# LIDO-HW_100_InputStage.net
KiCad netlist of a schematic drawn in Altium Designer
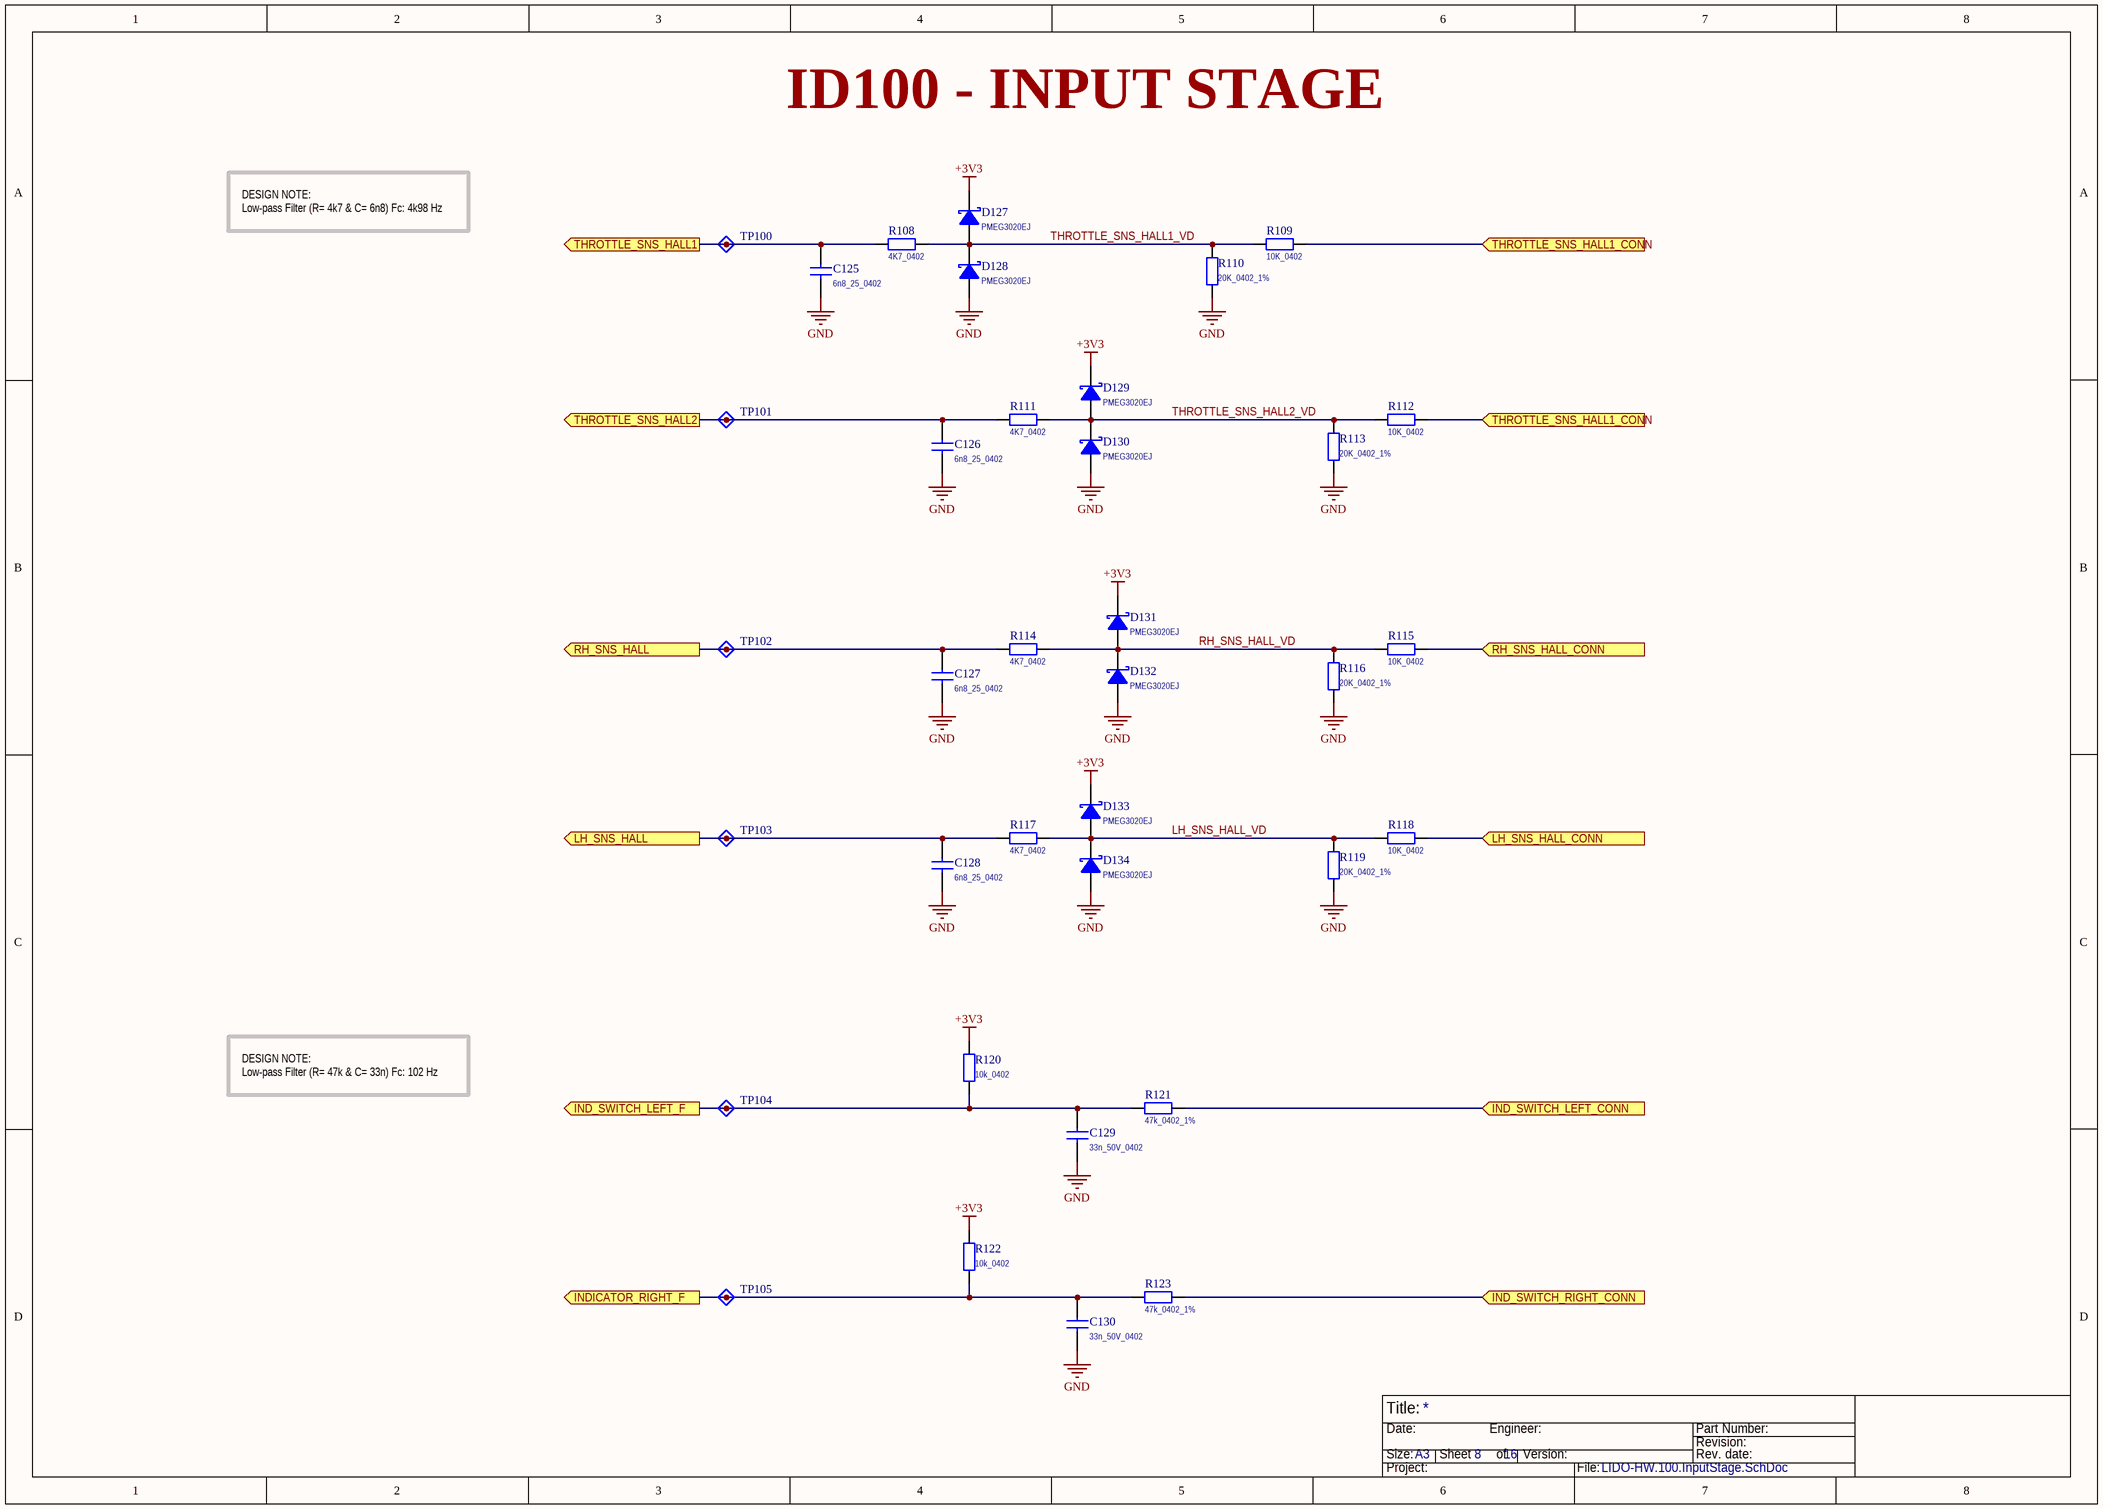
[diagram p0: LIDO-HW.100.InputStage.SchDoc]

(export (version "E")
  (design (tool "Eeschema 10.0.6"))
  (components
    (comp (ref "C125")
      (value "6n8_25_0402")
      (description "Ceramic CAP Symbol")
      (libsource (lib "01_Capacitors") (part "Ceramic"))
    )
    (comp (ref "C126")
      (value "6n8_25_0402")
      (description "Ceramic CAP Symbol")
      (libsource (lib "01_Capacitors") (part "Ceramic"))
    )
    (comp (ref "C127")
      (value "6n8_25_0402")
      (description "Ceramic CAP Symbol")
      (libsource (lib "01_Capacitors") (part "Ceramic"))
    )
    (comp (ref "C128")
      (value "6n8_25_0402")
      (description "Ceramic CAP Symbol")
      (libsource (lib "01_Capacitors") (part "Ceramic"))
    )
    (comp (ref "C129")
      (value "33n_50V_0402")
      (description "Ceramic CAP Symbol")
      (libsource (lib "01_Capacitors") (part "Ceramic"))
    )
    (comp (ref "C130")
      (value "33n_50V_0402")
      (description "Ceramic CAP Symbol")
      (libsource (lib "01_Capacitors") (part "Ceramic"))
    )
    (comp (ref "D127")
      (value "PMEG3020EJ")
      (description "Schottky Diode Symbol")
      (libsource (lib "06_Diodes") (part "Schottky_A"))
    )
    (comp (ref "D128")
      (value "PMEG3020EJ")
      (description "Schottky Diode Symbol")
      (libsource (lib "06_Diodes") (part "Schottky_A"))
    )
    (comp (ref "D129")
      (value "PMEG3020EJ")
      (description "Schottky Diode Symbol")
      (libsource (lib "06_Diodes") (part "Schottky_A"))
    )
    (comp (ref "D130")
      (value "PMEG3020EJ")
      (description "Schottky Diode Symbol")
      (libsource (lib "06_Diodes") (part "Schottky_A"))
    )
    (comp (ref "D131")
      (value "PMEG3020EJ")
      (description "Schottky Diode Symbol")
      (libsource (lib "06_Diodes") (part "Schottky_A"))
    )
    (comp (ref "D132")
      (value "PMEG3020EJ")
      (description "Schottky Diode Symbol")
      (libsource (lib "06_Diodes") (part "Schottky_A"))
    )
    (comp (ref "D133")
      (value "PMEG3020EJ")
      (description "Schottky Diode Symbol")
      (libsource (lib "06_Diodes") (part "Schottky_A"))
    )
    (comp (ref "D134")
      (value "PMEG3020EJ")
      (description "Schottky Diode Symbol")
      (libsource (lib "06_Diodes") (part "Schottky_A"))
    )
    (comp (ref "R108")
      (value "4K7_0402")
      (description "Resistor Symbol")
      (libsource (lib "") (part "Resistor_1"))
    )
    (comp (ref "R109")
      (value "10K_0402")
      (description "Resistor Symbol")
      (libsource (lib "") (part "Resistor_1"))
    )
    (comp (ref "R110")
      (value "20K_0402_1%")
      (description "Resistor Symbol")
      (libsource (lib "02_Resistors") (part "Resistor"))
    )
    (comp (ref "R111")
      (value "4K7_0402")
      (description "Resistor Symbol")
      (libsource (lib "") (part "Resistor_1"))
    )
    (comp (ref "R112")
      (value "10K_0402")
      (description "Resistor Symbol")
      (libsource (lib "") (part "Resistor_1"))
    )
    (comp (ref "R113")
      (value "20K_0402_1%")
      (description "Resistor Symbol")
      (libsource (lib "02_Resistors") (part "Resistor"))
    )
    (comp (ref "R114")
      (value "4K7_0402")
      (description "Resistor Symbol")
      (libsource (lib "") (part "Resistor_1"))
    )
    (comp (ref "R115")
      (value "10K_0402")
      (description "Resistor Symbol")
      (libsource (lib "") (part "Resistor_1"))
    )
    (comp (ref "R116")
      (value "20K_0402_1%")
      (description "Resistor Symbol")
      (libsource (lib "02_Resistors") (part "Resistor"))
    )
    (comp (ref "R117")
      (value "4K7_0402")
      (description "Resistor Symbol")
      (libsource (lib "") (part "Resistor_1"))
    )
    (comp (ref "R118")
      (value "10K_0402")
      (description "Resistor Symbol")
      (libsource (lib "") (part "Resistor_1"))
    )
    (comp (ref "R119")
      (value "20K_0402_1%")
      (description "Resistor Symbol")
      (libsource (lib "02_Resistors") (part "Resistor"))
    )
    (comp (ref "R120")
      (value "10k_0402")
      (description "Resistor Symbol")
      (libsource (lib "02_Resistors") (part "Resistor"))
    )
    (comp (ref "R121")
      (value "47k_0402_1%")
      (description "Resistor Symbol")
      (libsource (lib "") (part "Resistor_1"))
    )
    (comp (ref "R122")
      (value "10k_0402")
      (description "Resistor Symbol")
      (libsource (lib "02_Resistors") (part "Resistor"))
    )
    (comp (ref "R123")
      (value "47k_0402_1%")
      (description "Resistor Symbol")
      (libsource (lib "") (part "Resistor_1"))
    )
    (comp (ref "TP100")
      (value "TestPoint_A")
      (description "Test Point Symbol verion A")
      (libsource (lib "31_MFG_Elements") (part "TestPoint_A"))
    )
    (comp (ref "TP101")
      (value "TestPoint_A")
      (description "Test Point Symbol verion A")
      (libsource (lib "31_MFG_Elements") (part "TestPoint_A"))
    )
    (comp (ref "TP102")
      (value "TestPoint_A")
      (description "Test Point Symbol verion A")
      (libsource (lib "31_MFG_Elements") (part "TestPoint_A"))
    )
    (comp (ref "TP103")
      (value "TestPoint_A")
      (description "Test Point Symbol verion A")
      (libsource (lib "31_MFG_Elements") (part "TestPoint_A"))
    )
    (comp (ref "TP104")
      (value "TestPoint_A")
      (description "Test Point Symbol verion A")
      (libsource (lib "31_MFG_Elements") (part "TestPoint_A"))
    )
    (comp (ref "TP105")
      (value "TestPoint_A")
      (description "Test Point Symbol verion A")
      (libsource (lib "31_MFG_Elements") (part "TestPoint_A"))
    )
  )
  (nets
    (net (code "1") (name "+3V3") (class "Default")
      (node (ref "D127") (pin "C") (pinfunction "C_C") (pintype "passive"))
      (node (ref "D129") (pin "C") (pinfunction "C_C") (pintype "passive"))
      (node (ref "D131") (pin "C") (pinfunction "C_C") (pintype "passive"))
      (node (ref "D133") (pin "C") (pinfunction "C_C") (pintype "passive"))
      (node (ref "R120") (pin "2") (pinfunction "2_2") (pintype "passive"))
      (node (ref "R122") (pin "2") (pinfunction "2_2") (pintype "passive"))
    )
    (net (code "2") (name "/INDICATOR_RIGHT_F") (class "Default")
      (node (ref "C130") (pin "1") (pinfunction "1_1") (pintype "passive"))
      (node (ref "R122") (pin "1") (pinfunction "1_1") (pintype "passive"))
      (node (ref "R123") (pin "1") (pinfunction "1_1") (pintype "passive"))
      (node (ref "TP105") (pin "1") (pinfunction "TP_1") (pintype "passive"))
    )
    (net (code "3") (name "/IND_SWITCH_LEFT_CONN") (class "Default")
      (node (ref "R121") (pin "2") (pinfunction "2_2") (pintype "passive"))
    )
    (net (code "4") (name "/IND_SWITCH_LEFT_F") (class "Default")
      (node (ref "C129") (pin "1") (pinfunction "1_1") (pintype "passive"))
      (node (ref "R120") (pin "1") (pinfunction "1_1") (pintype "passive"))
      (node (ref "R121") (pin "1") (pinfunction "1_1") (pintype "passive"))
      (node (ref "TP104") (pin "1") (pinfunction "TP_1") (pintype "passive"))
    )
    (net (code "5") (name "/IND_SWITCH_RIGHT_CONN") (class "Default")
      (node (ref "R123") (pin "2") (pinfunction "2_2") (pintype "passive"))
    )
    (net (code "6") (name "/LH_SNS_HALL") (class "Default")
      (node (ref "C128") (pin "1") (pinfunction "1_1") (pintype "passive"))
      (node (ref "R117") (pin "1") (pinfunction "1_1") (pintype "passive"))
      (node (ref "TP103") (pin "1") (pinfunction "TP_1") (pintype "passive"))
    )
    (net (code "7") (name "/LH_SNS_HALL_CONN") (class "Default")
      (node (ref "R118") (pin "2") (pinfunction "2_2") (pintype "passive"))
    )
    (net (code "8") (name "/LH_SNS_HALL_VD") (class "Default")
      (node (ref "D133") (pin "A") (pinfunction "A_A") (pintype "passive"))
      (node (ref "D134") (pin "C") (pinfunction "C_C") (pintype "passive"))
      (node (ref "R117") (pin "2") (pinfunction "2_2") (pintype "passive"))
      (node (ref "R118") (pin "1") (pinfunction "1_1") (pintype "passive"))
      (node (ref "R119") (pin "2") (pinfunction "2_2") (pintype "passive"))
    )
    (net (code "9") (name "/RH_SNS_HALL") (class "Default")
      (node (ref "C127") (pin "1") (pinfunction "1_1") (pintype "passive"))
      (node (ref "R114") (pin "1") (pinfunction "1_1") (pintype "passive"))
      (node (ref "TP102") (pin "1") (pinfunction "TP_1") (pintype "passive"))
    )
    (net (code "10") (name "/RH_SNS_HALL_CONN") (class "Default")
      (node (ref "R115") (pin "2") (pinfunction "2_2") (pintype "passive"))
    )
    (net (code "11") (name "/RH_SNS_HALL_VD") (class "Default")
      (node (ref "D131") (pin "A") (pinfunction "A_A") (pintype "passive"))
      (node (ref "D132") (pin "C") (pinfunction "C_C") (pintype "passive"))
      (node (ref "R114") (pin "2") (pinfunction "2_2") (pintype "passive"))
      (node (ref "R115") (pin "1") (pinfunction "1_1") (pintype "passive"))
      (node (ref "R116") (pin "2") (pinfunction "2_2") (pintype "passive"))
    )
    (net (code "12") (name "/THROTTLE_SNS_HALL1") (class "Default")
      (node (ref "C125") (pin "1") (pinfunction "1_1") (pintype "passive"))
      (node (ref "R108") (pin "1") (pinfunction "1_1") (pintype "passive"))
      (node (ref "TP100") (pin "1") (pinfunction "TP_1") (pintype "passive"))
    )
    (net (code "13") (name "/THROTTLE_SNS_HALL1_CONN") (class "Default")
      (node (ref "R109") (pin "2") (pinfunction "2_2") (pintype "passive"))
      (node (ref "R112") (pin "2") (pinfunction "2_2") (pintype "passive"))
    )
    (net (code "14") (name "/THROTTLE_SNS_HALL1_VD") (class "Default")
      (node (ref "D127") (pin "A") (pinfunction "A_A") (pintype "passive"))
      (node (ref "D128") (pin "C") (pinfunction "C_C") (pintype "passive"))
      (node (ref "R108") (pin "2") (pinfunction "2_2") (pintype "passive"))
      (node (ref "R109") (pin "1") (pinfunction "1_1") (pintype "passive"))
      (node (ref "R110") (pin "2") (pinfunction "2_2") (pintype "passive"))
    )
    (net (code "15") (name "/THROTTLE_SNS_HALL2") (class "Default")
      (node (ref "C126") (pin "1") (pinfunction "1_1") (pintype "passive"))
      (node (ref "R111") (pin "1") (pinfunction "1_1") (pintype "passive"))
      (node (ref "TP101") (pin "1") (pinfunction "TP_1") (pintype "passive"))
    )
    (net (code "16") (name "/THROTTLE_SNS_HALL2_VD") (class "Default")
      (node (ref "D129") (pin "A") (pinfunction "A_A") (pintype "passive"))
      (node (ref "D130") (pin "C") (pinfunction "C_C") (pintype "passive"))
      (node (ref "R111") (pin "2") (pinfunction "2_2") (pintype "passive"))
      (node (ref "R112") (pin "1") (pinfunction "1_1") (pintype "passive"))
      (node (ref "R113") (pin "2") (pinfunction "2_2") (pintype "passive"))
    )
    (net (code "17") (name "GND") (class "Default")
      (node (ref "C125") (pin "2") (pinfunction "2_2") (pintype "passive"))
      (node (ref "C126") (pin "2") (pinfunction "2_2") (pintype "passive"))
      (node (ref "C127") (pin "2") (pinfunction "2_2") (pintype "passive"))
      (node (ref "C128") (pin "2") (pinfunction "2_2") (pintype "passive"))
      (node (ref "C129") (pin "2") (pinfunction "2_2") (pintype "passive"))
      (node (ref "C130") (pin "2") (pinfunction "2_2") (pintype "passive"))
      (node (ref "D128") (pin "A") (pinfunction "A_A") (pintype "passive"))
      (node (ref "D130") (pin "A") (pinfunction "A_A") (pintype "passive"))
      (node (ref "D132") (pin "A") (pinfunction "A_A") (pintype "passive"))
      (node (ref "D134") (pin "A") (pinfunction "A_A") (pintype "passive"))
      (node (ref "R110") (pin "1") (pinfunction "1_1") (pintype "passive"))
      (node (ref "R113") (pin "1") (pinfunction "1_1") (pintype "passive"))
      (node (ref "R116") (pin "1") (pinfunction "1_1") (pintype "passive"))
      (node (ref "R119") (pin "1") (pinfunction "1_1") (pintype "passive"))
    )
  )
)
